# VSCard_v3.net
KiCad netlist of a schematic drawn in EAGLE
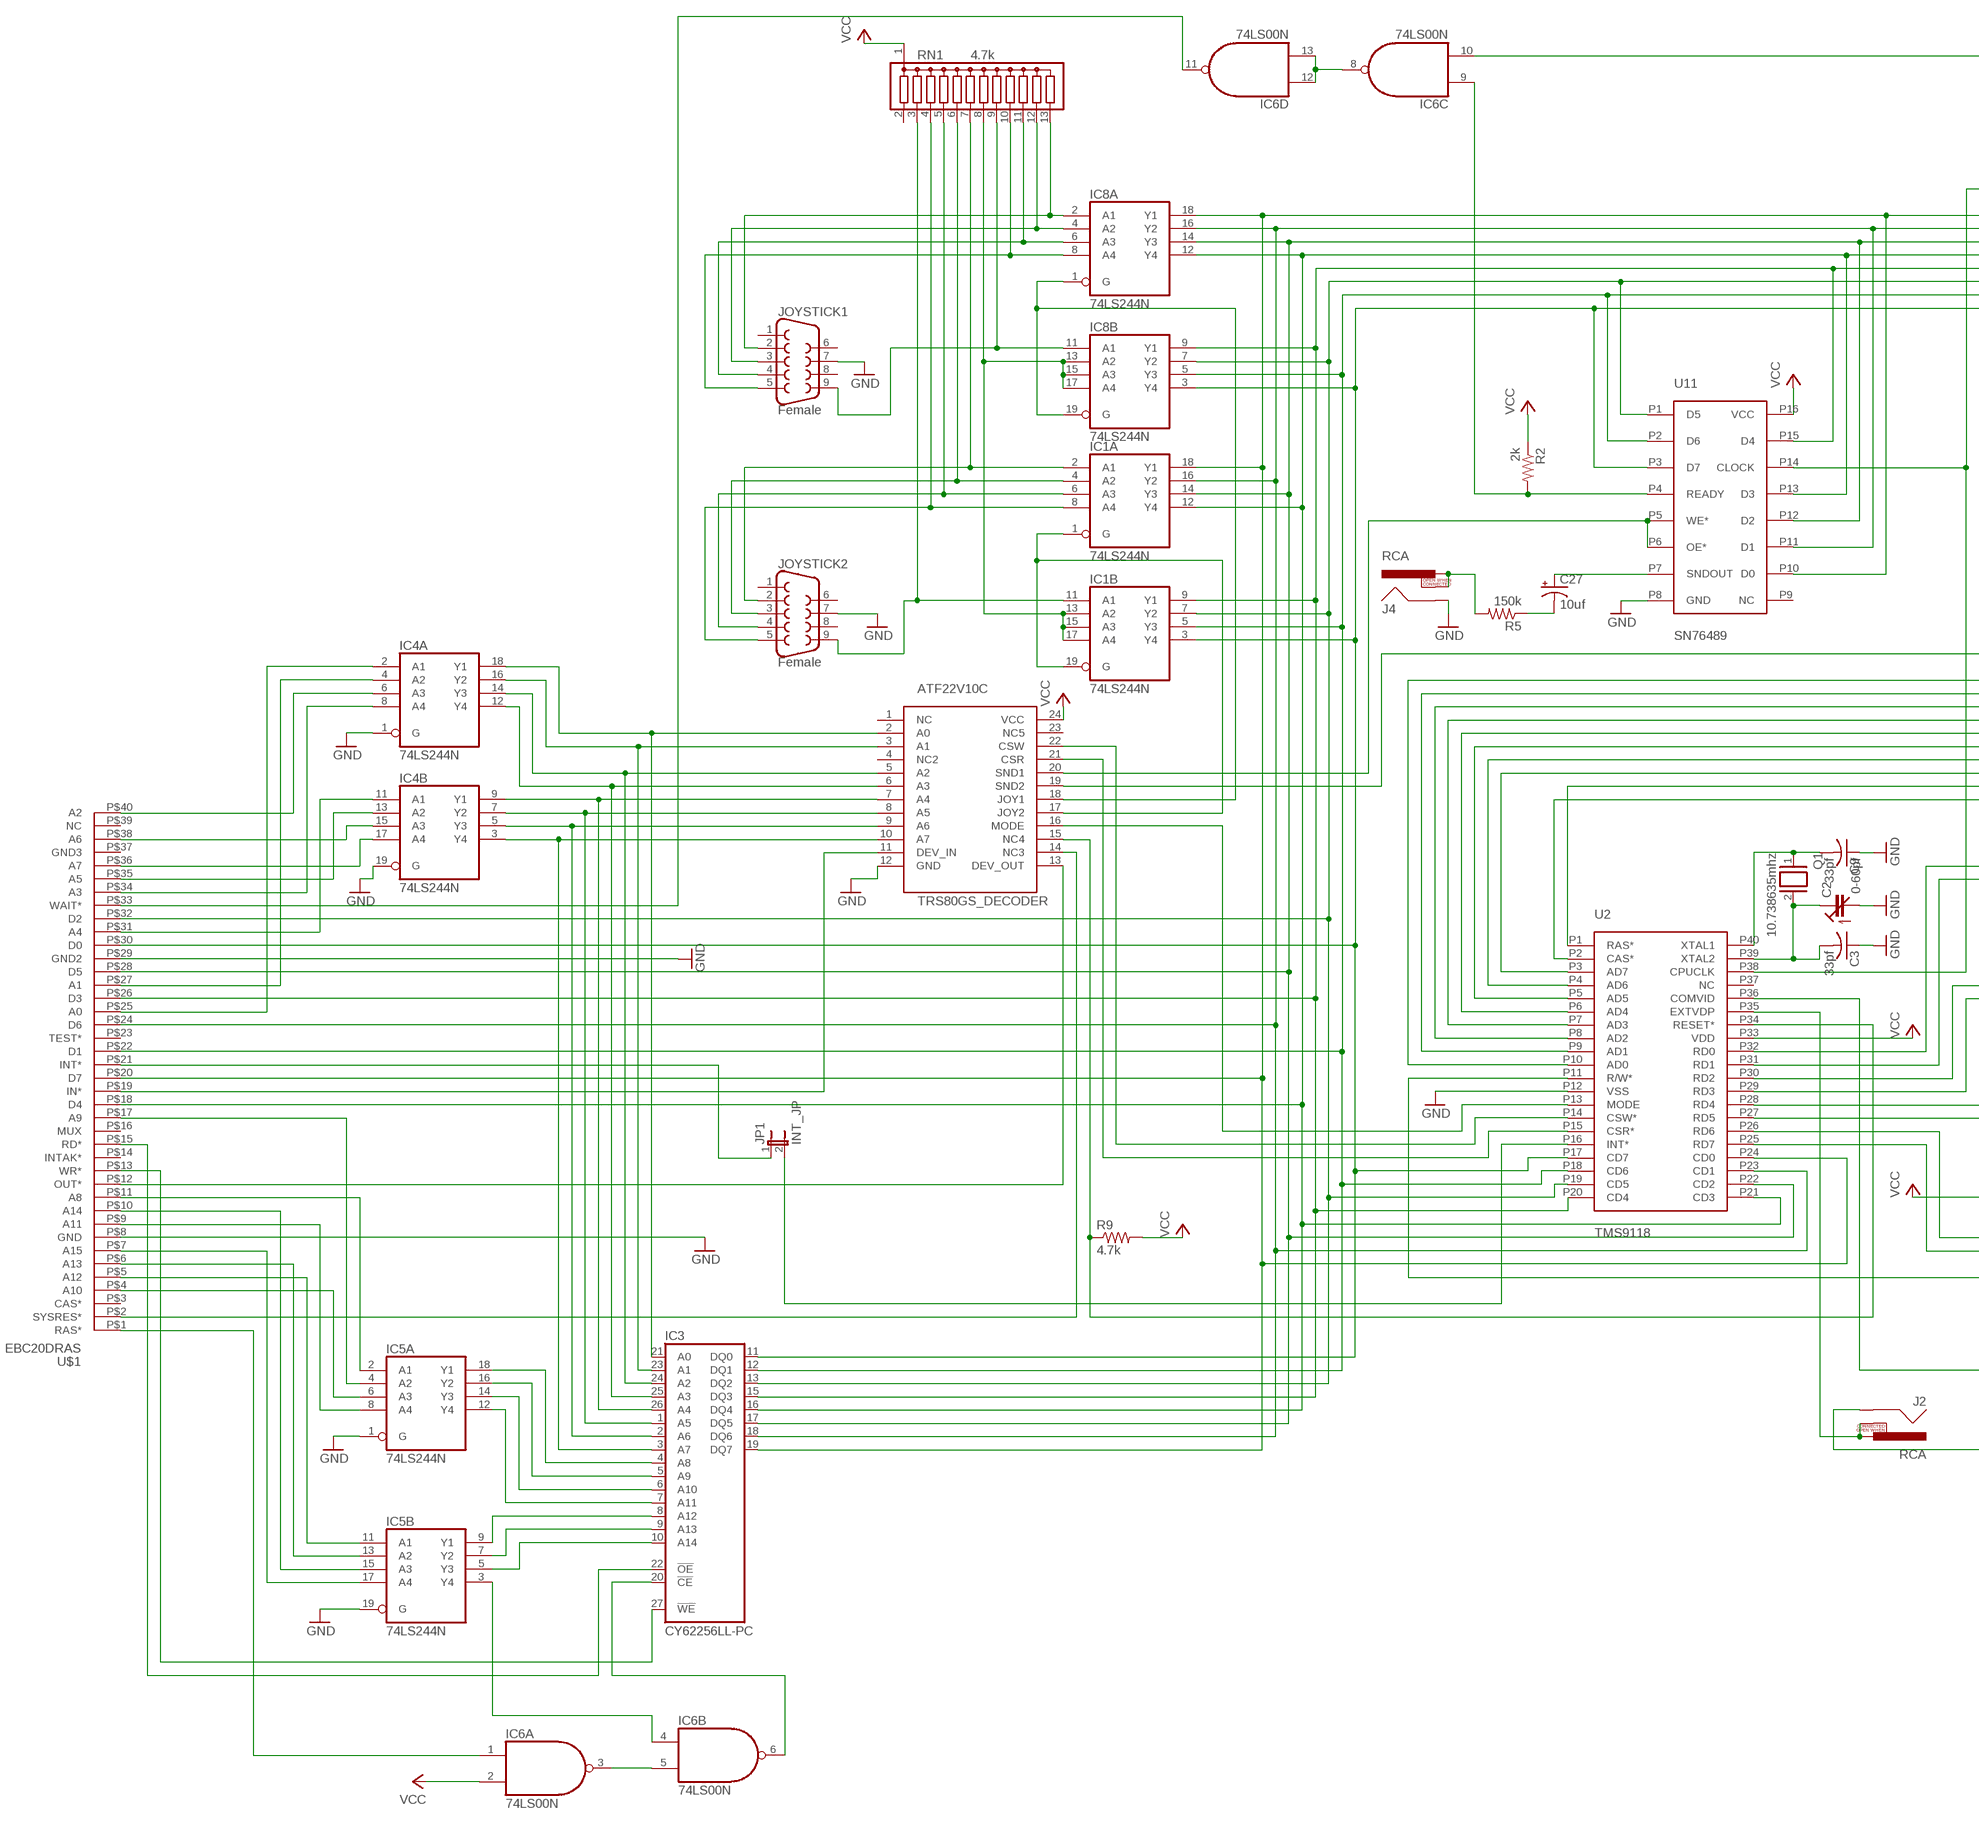
[diagram p0: schematic, sheet 1, part 1 of 2]
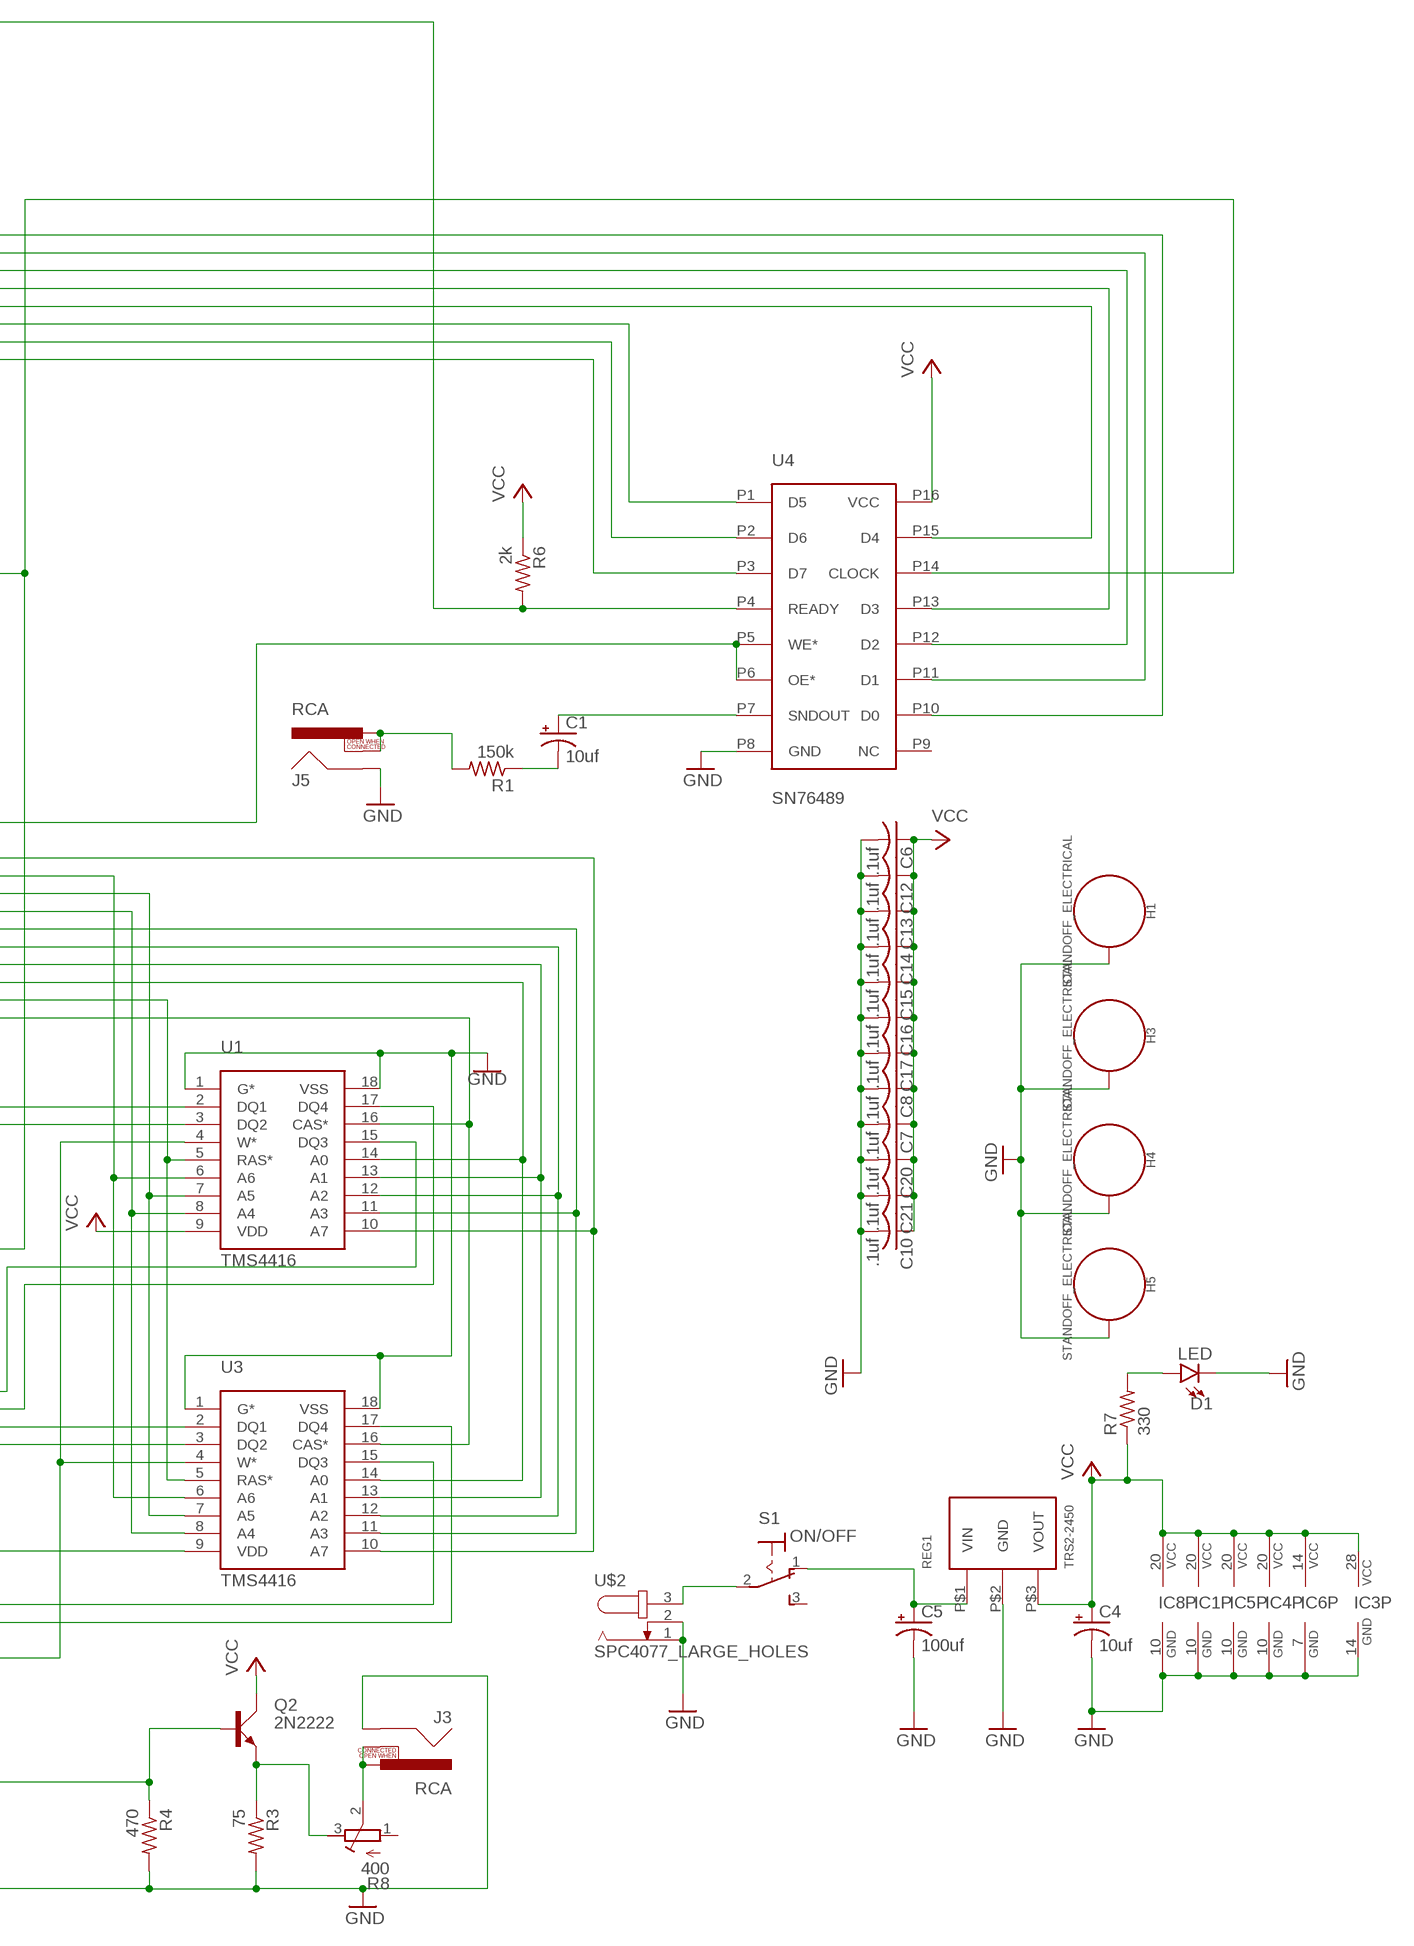
[diagram p1: schematic, sheet 1, part 2 of 2]

(export (version "E")
  (design (tool "Eeschema 10.0.6"))
  (components
    (comp (ref "ATF22V10C")
      (value "TRS80GS_DECODER")
      (footprint "eagle-import:DIP24SKI")
      (libsource (lib "eagle-import") (part "TRS80GS_DECODER"))
    )
    (comp (ref "C1")
      (value "10uf")
      (footprint "eagle-import:E2,5-6")
      (libsource (lib "eagle-import") (part "resistor_348_CPOL-USE2.5-6"))
    )
    (comp (ref "C2")
      (value "0-60pf")
      (footprint "eagle-import:CTRIM3050.504")
      (libsource (lib "eagle-import") (part "C-TRIMM3050.504"))
    )
    (comp (ref "C3")
      (value "33pf")
      (footprint "eagle-import:C050-050X075")
      (libsource (lib "eagle-import") (part "C-US050-050X075"))
    )
    (comp (ref "C4")
      (value "10uf")
      (footprint "eagle-import:E2,5-5")
      (libsource (lib "eagle-import") (part "resistor_348_CPOL-USE2.5-5"))
    )
    (comp (ref "C5")
      (value "100uf")
      (footprint "eagle-import:E3,5-10")
      (libsource (lib "eagle-import") (part "CPOL-USE3.5-10"))
    )
    (comp (ref "C6")
      (value ".1uf")
      (footprint "eagle-import:C025-025X050")
      (libsource (lib "eagle-import") (part "resistor_348_C-US025-025X050"))
    )
    (comp (ref "C7")
      (value ".1uf")
      (footprint "eagle-import:C025-025X050")
      (libsource (lib "eagle-import") (part "resistor_348_C-US025-025X050"))
    )
    (comp (ref "C8")
      (value ".1uf")
      (footprint "eagle-import:C025-025X050")
      (libsource (lib "eagle-import") (part "resistor_348_C-US025-025X050"))
    )
    (comp (ref "C9")
      (value "33pf")
      (footprint "eagle-import:C050-050X075")
      (libsource (lib "eagle-import") (part "C-US050-050X075"))
    )
    (comp (ref "C10")
      (value ".1uf")
      (footprint "eagle-import:C025-025X050")
      (libsource (lib "eagle-import") (part "resistor_348_C-US025-025X050"))
    )
    (comp (ref "C12")
      (value ".1uf")
      (footprint "eagle-import:C025-025X050")
      (libsource (lib "eagle-import") (part "resistor_348_C-US025-025X050"))
    )
    (comp (ref "C13")
      (value ".1uf")
      (footprint "eagle-import:C025-025X050")
      (libsource (lib "eagle-import") (part "resistor_348_C-US025-025X050"))
    )
    (comp (ref "C14")
      (value ".1uf")
      (footprint "eagle-import:C025-025X050")
      (libsource (lib "eagle-import") (part "resistor_348_C-US025-025X050"))
    )
    (comp (ref "C15")
      (value ".1uf")
      (footprint "eagle-import:C025-025X050")
      (libsource (lib "eagle-import") (part "resistor_348_C-US025-025X050"))
    )
    (comp (ref "C16")
      (value ".1uf")
      (footprint "eagle-import:C025-025X050")
      (libsource (lib "eagle-import") (part "resistor_348_C-US025-025X050"))
    )
    (comp (ref "C17")
      (value ".1uf")
      (footprint "eagle-import:C025-025X050")
      (libsource (lib "eagle-import") (part "resistor_348_C-US025-025X050"))
    )
    (comp (ref "C20")
      (value ".1uf")
      (footprint "eagle-import:C025-025X050")
      (libsource (lib "eagle-import") (part "resistor_348_C-US025-025X050"))
    )
    (comp (ref "C21")
      (value ".1uf")
      (footprint "eagle-import:C025-025X050")
      (libsource (lib "eagle-import") (part "resistor_348_C-US025-025X050"))
    )
    (comp (ref "C27")
      (value "10uf")
      (footprint "eagle-import:E2,5-6")
      (libsource (lib "eagle-import") (part "resistor_348_CPOL-USE2.5-6"))
    )
    (comp (ref "D1")
      (value "LED")
      (footprint "eagle-import:LED_3MM")
      (libsource (lib "eagle-import") (part "LED3MM"))
    )
    (comp (ref "H1")
      (value "STANDOFF_ELECTRICAL")
      (footprint "eagle-import:STANDOFF-ELECTRICAL")
      (libsource (lib "eagle-import") (part "STANDOFF_ELECTRICAL"))
    )
    (comp (ref "H3")
      (value "STANDOFF_ELECTRICAL")
      (footprint "eagle-import:STANDOFF-ELECTRICAL")
      (libsource (lib "eagle-import") (part "STANDOFF_ELECTRICAL"))
    )
    (comp (ref "H4")
      (value "STANDOFF_ELECTRICAL")
      (footprint "eagle-import:STANDOFF-ELECTRICAL")
      (libsource (lib "eagle-import") (part "STANDOFF_ELECTRICAL"))
    )
    (comp (ref "H5")
      (value "STANDOFF_ELECTRICAL")
      (footprint "eagle-import:STANDOFF-ELECTRICAL")
      (libsource (lib "eagle-import") (part "STANDOFF_ELECTRICAL"))
    )
    (comp (ref "IC1")
      (value "74LS244N")
      (footprint "eagle-import:DIL20")
      (libsource (lib "eagle-import") (part "74244NLS"))
    )
    (comp (ref "IC3")
      (value "CY62256LL-PC")
      (footprint "eagle-import:DIL28-6")
      (libsource (lib "eagle-import") (part "CY62256LL-?PC"))
    )
    (comp (ref "IC4")
      (value "74LS244N")
      (footprint "eagle-import:DIL20")
      (libsource (lib "eagle-import") (part "74244NLS"))
    )
    (comp (ref "IC5")
      (value "74LS244N")
      (footprint "eagle-import:DIL20")
      (libsource (lib "eagle-import") (part "74244NLS"))
    )
    (comp (ref "IC6")
      (value "74LS00N")
      (footprint "eagle-import:DIL14")
      (libsource (lib "eagle-import") (part "7400NLS"))
    )
    (comp (ref "IC8")
      (value "74LS244N")
      (footprint "eagle-import:DIL20")
      (libsource (lib "eagle-import") (part "74244NLS"))
    )
    (comp (ref "J2")
      (value "RCA")
      (footprint "eagle-import:RCA")
      (libsource (lib "eagle-import") (part "RCA"))
    )
    (comp (ref "J3")
      (value "RCA")
      (footprint "eagle-import:RCA")
      (libsource (lib "eagle-import") (part "RCA"))
    )
    (comp (ref "J4")
      (value "RCA")
      (footprint "eagle-import:RCA")
      (libsource (lib "eagle-import") (part "RCA"))
    )
    (comp (ref "J5")
      (value "RCA")
      (footprint "eagle-import:RCA")
      (libsource (lib "eagle-import") (part "RCA"))
    )
    (comp (ref "JOYSTICK1")
      (value "Female")
      (footprint "eagle-import:DB9")
      (libsource (lib "eagle-import") (part "DB9FEMALE"))
    )
    (comp (ref "JOYSTICK2")
      (value "Female")
      (footprint "eagle-import:DB9")
      (libsource (lib "eagle-import") (part "DB9FEMALE"))
    )
    (comp (ref "JP1")
      (value "INT_JP")
      (footprint "eagle-import:JP1")
      (libsource (lib "eagle-import") (part "JP1E"))
    )
    (comp (ref "Q1")
      (value "10.738635mhz")
      (footprint "eagle-import:QS")
      (libsource (lib "eagle-import") (part "XTAL/S"))
    )
    (comp (ref "Q2")
      (value "2N2222")
      (footprint "eagle-import:TO18A")
      (libsource (lib "eagle-import") (part "2N2222"))
    )
    (comp (ref "R1")
      (value "150k")
      (footprint "eagle-import:0207_2V")
      (libsource (lib "eagle-import") (part "R-US_0207/2V"))
    )
    (comp (ref "R2")
      (value "2k")
      (footprint "eagle-import:0207_2V")
      (libsource (lib "eagle-import") (part "R-US_0207/2V"))
    )
    (comp (ref "R3")
      (value "75")
      (footprint "eagle-import:0207_2V")
      (libsource (lib "eagle-import") (part "R-US_0207/2V"))
    )
    (comp (ref "R4")
      (value "470")
      (footprint "eagle-import:0207_2V")
      (libsource (lib "eagle-import") (part "R-US_0207/2V"))
    )
    (comp (ref "R5")
      (value "150k")
      (footprint "eagle-import:0207_2V")
      (libsource (lib "eagle-import") (part "R-US_0207/2V"))
    )
    (comp (ref "R6")
      (value "2k")
      (footprint "eagle-import:0207_2V")
      (libsource (lib "eagle-import") (part "R-US_0207/2V"))
    )
    (comp (ref "R7")
      (value "330")
      (footprint "eagle-import:0309V")
      (libsource (lib "eagle-import") (part "R-US_0309/V"))
    )
    (comp (ref "R8")
      (value "400")
      (footprint "eagle-import:RTRIM64W")
      (libsource (lib "eagle-import") (part "R-TRIMM64W"))
    )
    (comp (ref "R9")
      (value "4.7k")
      (footprint "eagle-import:0207_2V")
      (libsource (lib "eagle-import") (part "R-US_0207/2V"))
    )
    (comp (ref "REG1")
      (value "TRS2-2450")
      (footprint "eagle-import:TRACON_REG")
      (libsource (lib "eagle-import") (part "TRS2-2450"))
    )
    (comp (ref "RN1")
      (value "4.7k")
      (footprint "eagle-import:SIL13")
      (libsource (lib "eagle-import") (part "G12R"))
    )
    (comp (ref "S1")
      (value "ON/OFF")
      (footprint "eagle-import:320-916")
      (libsource (lib "eagle-import") (part "320-916"))
    )
    (comp (ref "U$1")
      (value "EBC20DRAS")
      (footprint "eagle-import:EBC20DRAS")
      (libsource (lib "eagle-import") (part "EBC20DRAS"))
    )
    (comp (ref "U$2")
      (value "SPC4077_LARGE_HOLES")
      (footprint "eagle-import:SPC4077")
      (libsource (lib "eagle-import") (part "SPC4077_LARGE_HOLES"))
    )
    (comp (ref "U1")
      (value "TMS4416")
      (footprint "eagle-import:DIP18")
      (libsource (lib "eagle-import") (part "TMS4416"))
    )
    (comp (ref "U2")
      (value "TMS9118")
      (footprint "eagle-import:DIP40_MCU")
      (libsource (lib "eagle-import") (part "TMS9118"))
    )
    (comp (ref "U3")
      (value "TMS4416")
      (footprint "eagle-import:DIP18")
      (libsource (lib "eagle-import") (part "TMS4416"))
    )
    (comp (ref "U4")
      (value "SN76489")
      (footprint "eagle-import:DIP16")
      (libsource (lib "eagle-import") (part "SN76489"))
    )
    (comp (ref "U11")
      (value "SN76489")
      (footprint "eagle-import:DIP16")
      (libsource (lib "eagle-import") (part "SN76489"))
    )
  )
  (nets
    (net (code "1") (name "GND") (class "Default")
      (node (ref "ATF22V10C") (pin "12") (pinfunction "GND_12") (pintype "bidirectional"))
      (node (ref "C10") (pin "2") (pinfunction "2_2") (pintype "passive"))
      (node (ref "C12") (pin "2") (pinfunction "2_2") (pintype "passive"))
      (node (ref "C13") (pin "2") (pinfunction "2_2") (pintype "passive"))
      (node (ref "C14") (pin "2") (pinfunction "2_2") (pintype "passive"))
      (node (ref "C15") (pin "2") (pinfunction "2_2") (pintype "passive"))
      (node (ref "C16") (pin "2") (pinfunction "2_2") (pintype "passive"))
      (node (ref "C17") (pin "2") (pinfunction "2_2") (pintype "passive"))
      (node (ref "C2") (pin "2") (pinfunction "A_2") (pintype "passive"))
      (node (ref "C20") (pin "2") (pinfunction "2_2") (pintype "passive"))
      (node (ref "C21") (pin "2") (pinfunction "2_2") (pintype "passive"))
      (node (ref "C3") (pin "1") (pinfunction "1_1") (pintype "passive"))
      (node (ref "C4") (pin "-") (pinfunction "-_-") (pintype "passive"))
      (node (ref "C5") (pin "-") (pinfunction "-_-") (pintype "passive"))
      (node (ref "C6") (pin "2") (pinfunction "2_2") (pintype "passive"))
      (node (ref "C7") (pin "2") (pinfunction "2_2") (pintype "passive"))
      (node (ref "C8") (pin "2") (pinfunction "2_2") (pintype "passive"))
      (node (ref "C9") (pin "1") (pinfunction "1_1") (pintype "passive"))
      (node (ref "D1") (pin "K") (pinfunction "C_K") (pintype "passive"))
      (node (ref "H1") (pin "P1") (pinfunction "P$1_P1") (pintype "bidirectional"))
      (node (ref "H3") (pin "P1") (pinfunction "P$1_P1") (pintype "bidirectional"))
      (node (ref "H4") (pin "P1") (pinfunction "P$1_P1") (pintype "bidirectional"))
      (node (ref "H5") (pin "P1") (pinfunction "P$1_P1") (pintype "bidirectional"))
      (node (ref "IC1") (pin "10") (pinfunction "GND_10") (pintype "power_in"))
      (node (ref "IC3") (pin "14") (pinfunction "GND_14") (pintype "power_in"))
      (node (ref "IC4") (pin "1") (pinfunction "G_1") (pintype "input"))
      (node (ref "IC4") (pin "10") (pinfunction "GND_10") (pintype "power_in"))
      (node (ref "IC4") (pin "19") (pinfunction "G_19") (pintype "input"))
      (node (ref "IC5") (pin "1") (pinfunction "G_1") (pintype "input"))
      (node (ref "IC5") (pin "10") (pinfunction "GND_10") (pintype "power_in"))
      (node (ref "IC5") (pin "19") (pinfunction "G_19") (pintype "input"))
      (node (ref "IC6") (pin "7") (pinfunction "GND_7") (pintype "power_in"))
      (node (ref "IC8") (pin "10") (pinfunction "GND_10") (pintype "power_in"))
      (node (ref "J2") (pin "SHELL") (pinfunction "SHELL_SHELL") (pintype "bidirectional"))
      (node (ref "J3") (pin "SHELL") (pinfunction "SHELL_SHELL") (pintype "bidirectional"))
      (node (ref "J4") (pin "SHELL") (pinfunction "SHELL_SHELL") (pintype "bidirectional"))
      (node (ref "J5") (pin "SHELL") (pinfunction "SHELL_SHELL") (pintype "bidirectional"))
      (node (ref "JOYSTICK1") (pin "7") (pinfunction "7_7") (pintype "passive"))
      (node (ref "JOYSTICK2") (pin "7") (pinfunction "7_7") (pintype "passive"))
      (node (ref "R3") (pin "2") (pinfunction "2_2") (pintype "passive"))
      (node (ref "R4") (pin "2") (pinfunction "2_2") (pintype "passive"))
      (node (ref "REG1") (pin "P$2") (pinfunction "GND_P$2") (pintype "bidirectional"))
      (node (ref "U$1") (pin "P$29") (pinfunction "GND2_P$29") (pintype "bidirectional"))
      (node (ref "U$1") (pin "P$8") (pinfunction "GND_P$8") (pintype "bidirectional"))
      (node (ref "U$2") (pin "1") (pinfunction "1_1") (pintype "passive"))
      (node (ref "U$2") (pin "2") (pinfunction "2_2") (pintype "passive"))
      (node (ref "U1") (pin "1") (pinfunction "G*_1") (pintype "bidirectional"))
      (node (ref "U1") (pin "18") (pinfunction "VSS_18") (pintype "bidirectional"))
      (node (ref "U11") (pin "P8") (pinfunction "GND_P8") (pintype "bidirectional"))
      (node (ref "U2") (pin "P12") (pinfunction "VSS_P12") (pintype "bidirectional"))
      (node (ref "U3") (pin "1") (pinfunction "G*_1") (pintype "bidirectional"))
      (node (ref "U3") (pin "18") (pinfunction "VSS_18") (pintype "bidirectional"))
      (node (ref "U4") (pin "P8") (pinfunction "GND_P8") (pintype "bidirectional"))
    )
    (net (code "2") (name "Net-(ATF22V10C-A0)") (class "Default")
      (node (ref "ATF22V10C") (pin "2") (pinfunction "A0_2") (pintype "bidirectional"))
      (node (ref "IC3") (pin "21") (pinfunction "A0_21") (pintype "input"))
      (node (ref "IC4") (pin "18") (pinfunction "Y1_18") (pintype "tri_state"))
    )
    (net (code "3") (name "Net-(ATF22V10C-A1)") (class "Default")
      (node (ref "ATF22V10C") (pin "3") (pinfunction "A1_3") (pintype "bidirectional"))
      (node (ref "IC3") (pin "23") (pinfunction "A1_23") (pintype "input"))
      (node (ref "IC4") (pin "16") (pinfunction "Y2_16") (pintype "tri_state"))
    )
    (net (code "4") (name "Net-(ATF22V10C-A2)") (class "Default")
      (node (ref "ATF22V10C") (pin "5") (pinfunction "A2_5") (pintype "bidirectional"))
      (node (ref "IC3") (pin "24") (pinfunction "A2_24") (pintype "input"))
      (node (ref "IC4") (pin "14") (pinfunction "Y3_14") (pintype "tri_state"))
    )
    (net (code "5") (name "Net-(ATF22V10C-A3)") (class "Default")
      (node (ref "ATF22V10C") (pin "6") (pinfunction "A3_6") (pintype "bidirectional"))
      (node (ref "IC3") (pin "25") (pinfunction "A3_25") (pintype "input"))
      (node (ref "IC4") (pin "12") (pinfunction "Y4_12") (pintype "tri_state"))
    )
    (net (code "6") (name "Net-(ATF22V10C-A4)") (class "Default")
      (node (ref "ATF22V10C") (pin "7") (pinfunction "A4_7") (pintype "bidirectional"))
      (node (ref "IC3") (pin "26") (pinfunction "A4_26") (pintype "input"))
      (node (ref "IC4") (pin "9") (pinfunction "Y1_9") (pintype "tri_state"))
    )
    (net (code "7") (name "Net-(ATF22V10C-A5)") (class "Default")
      (node (ref "ATF22V10C") (pin "8") (pinfunction "A5_8") (pintype "bidirectional"))
      (node (ref "IC3") (pin "1") (pinfunction "A5_1") (pintype "input"))
      (node (ref "IC4") (pin "7") (pinfunction "Y2_7") (pintype "tri_state"))
    )
    (net (code "8") (name "Net-(ATF22V10C-A6)") (class "Default")
      (node (ref "ATF22V10C") (pin "9") (pinfunction "A6_9") (pintype "bidirectional"))
      (node (ref "IC3") (pin "2") (pinfunction "A6_2") (pintype "input"))
      (node (ref "IC4") (pin "5") (pinfunction "Y3_5") (pintype "tri_state"))
    )
    (net (code "9") (name "Net-(ATF22V10C-A7)") (class "Default")
      (node (ref "ATF22V10C") (pin "10") (pinfunction "A7_10") (pintype "bidirectional"))
      (node (ref "IC3") (pin "3") (pinfunction "A7_3") (pintype "input"))
      (node (ref "IC4") (pin "3") (pinfunction "Y4_3") (pintype "tri_state"))
    )
    (net (code "10") (name "Net-(ATF22V10C-CSR)") (class "Default")
      (node (ref "ATF22V10C") (pin "21") (pinfunction "CSR_21") (pintype "bidirectional"))
      (node (ref "U2") (pin "P15") (pinfunction "CSR*_P15") (pintype "bidirectional"))
    )
    (net (code "11") (name "Net-(ATF22V10C-CSW)") (class "Default")
      (node (ref "ATF22V10C") (pin "22") (pinfunction "CSW_22") (pintype "bidirectional"))
      (node (ref "U2") (pin "P14") (pinfunction "CSW*_P14") (pintype "bidirectional"))
    )
    (net (code "12") (name "Net-(ATF22V10C-DEV_IN)") (class "Default")
      (node (ref "ATF22V10C") (pin "11") (pinfunction "DEV_IN_11") (pintype "bidirectional"))
      (node (ref "U$1") (pin "P$19") (pinfunction "IN*_P$19") (pintype "bidirectional"))
    )
    (net (code "13") (name "Net-(ATF22V10C-DEV_OUT)") (class "Default")
      (node (ref "ATF22V10C") (pin "13") (pinfunction "DEV_OUT_13") (pintype "bidirectional"))
      (node (ref "U$1") (pin "P$12") (pinfunction "OUT*_P$12") (pintype "bidirectional"))
    )
    (net (code "14") (name "Net-(ATF22V10C-JOY1)") (class "Default")
      (node (ref "ATF22V10C") (pin "18") (pinfunction "JOY1_18") (pintype "bidirectional"))
      (node (ref "IC8") (pin "1") (pinfunction "G_1") (pintype "input"))
      (node (ref "IC8") (pin "19") (pinfunction "G_19") (pintype "input"))
    )
    (net (code "15") (name "Net-(ATF22V10C-JOY2)") (class "Default")
      (node (ref "ATF22V10C") (pin "17") (pinfunction "JOY2_17") (pintype "bidirectional"))
      (node (ref "IC1") (pin "1") (pinfunction "G_1") (pintype "input"))
      (node (ref "IC1") (pin "19") (pinfunction "G_19") (pintype "input"))
    )
    (net (code "16") (name "Net-(ATF22V10C-MODE)") (class "Default")
      (node (ref "ATF22V10C") (pin "16") (pinfunction "MODE_16") (pintype "bidirectional"))
      (node (ref "U2") (pin "P13") (pinfunction "MODE_P13") (pintype "bidirectional"))
    )
    (net (code "17") (name "Net-(ATF22V10C-NC3)") (class "Default")
      (node (ref "ATF22V10C") (pin "14") (pinfunction "NC3_14") (pintype "bidirectional"))
      (node (ref "U$1") (pin "P$2") (pinfunction "SYSRES*_P$2") (pintype "bidirectional"))
    )
    (net (code "18") (name "Net-(ATF22V10C-NC4)") (class "Default")
      (node (ref "ATF22V10C") (pin "15") (pinfunction "NC4_15") (pintype "bidirectional"))
      (node (ref "R9") (pin "1") (pinfunction "1_1") (pintype "passive"))
      (node (ref "U2") (pin "P34") (pinfunction "RESET*_P34") (pintype "bidirectional"))
    )
    (net (code "19") (name "Net-(ATF22V10C-SND1)") (class "Default")
      (node (ref "ATF22V10C") (pin "20") (pinfunction "SND1_20") (pintype "bidirectional"))
      (node (ref "U11") (pin "P5") (pinfunction "WE*_P5") (pintype "bidirectional"))
      (node (ref "U11") (pin "P6") (pinfunction "OE*_P6") (pintype "bidirectional"))
    )
    (net (code "20") (name "Net-(ATF22V10C-SND2)") (class "Default")
      (node (ref "ATF22V10C") (pin "19") (pinfunction "SND2_19") (pintype "bidirectional"))
      (node (ref "U4") (pin "P5") (pinfunction "WE*_P5") (pintype "bidirectional"))
      (node (ref "U4") (pin "P6") (pinfunction "OE*_P6") (pintype "bidirectional"))
    )
    (net (code "21") (name "Net-(C1-Pad-)") (class "Default")
      (node (ref "C1") (pin "-") (pinfunction "-_-") (pintype "passive"))
      (node (ref "R1") (pin "1") (pinfunction "1_1") (pintype "passive"))
    )
    (net (code "22") (name "Net-(C2-E)") (class "Default")
      (node (ref "C2") (pin "1") (pinfunction "E_1") (pintype "passive"))
      (node (ref "C3") (pin "2") (pinfunction "2_2") (pintype "passive"))
      (node (ref "Q1") (pin "2") (pinfunction "2_2") (pintype "passive"))
      (node (ref "U2") (pin "P39") (pinfunction "XTAL2_P39") (pintype "bidirectional"))
    )
    (net (code "23") (name "Net-(C27-Pad-)") (class "Default")
      (node (ref "C27") (pin "-") (pinfunction "-_-") (pintype "passive"))
      (node (ref "R5") (pin "1") (pinfunction "1_1") (pintype "passive"))
    )
    (net (code "24") (name "Net-(D1-PadA)") (class "Default")
      (node (ref "D1") (pin "A") (pinfunction "A_A") (pintype "passive"))
      (node (ref "R7") (pin "2") (pinfunction "2_2") (pintype "passive"))
    )
    (net (code "25") (name "Net-(IC1A-A1)") (class "Default")
      (node (ref "IC1") (pin "2") (pinfunction "A1_2") (pintype "input"))
      (node (ref "JOYSTICK2") (pin "2") (pinfunction "2_2") (pintype "passive"))
      (node (ref "RN1") (pin "7") (pinfunction "7_7") (pintype "passive"))
    )
    (net (code "26") (name "Net-(IC1A-A2)") (class "Default")
      (node (ref "IC1") (pin "4") (pinfunction "A2_4") (pintype "input"))
      (node (ref "JOYSTICK2") (pin "3") (pinfunction "3_3") (pintype "passive"))
      (node (ref "RN1") (pin "6") (pinfunction "6_6") (pintype "passive"))
    )
    (net (code "27") (name "Net-(IC1A-A3)") (class "Default")
      (node (ref "IC1") (pin "6") (pinfunction "A3_6") (pintype "input"))
      (node (ref "JOYSTICK2") (pin "4") (pinfunction "4_4") (pintype "passive"))
      (node (ref "RN1") (pin "5") (pinfunction "5_5") (pintype "passive"))
    )
    (net (code "28") (name "Net-(IC1A-A4)") (class "Default")
      (node (ref "IC1") (pin "8") (pinfunction "A4_8") (pintype "input"))
      (node (ref "JOYSTICK2") (pin "5") (pinfunction "5_5") (pintype "passive"))
      (node (ref "RN1") (pin "4") (pinfunction "4_4") (pintype "passive"))
    )
    (net (code "29") (name "Net-(IC1A-Y1)") (class "Default")
      (node (ref "IC1") (pin "18") (pinfunction "Y1_18") (pintype "tri_state"))
      (node (ref "IC3") (pin "19") (pinfunction "DQ7_19") (pintype "bidirectional"))
      (node (ref "IC8") (pin "18") (pinfunction "Y1_18") (pintype "tri_state"))
      (node (ref "U$1") (pin "P$20") (pinfunction "D7_P$20") (pintype "bidirectional"))
      (node (ref "U11") (pin "P10") (pinfunction "D0_P10") (pintype "bidirectional"))
      (node (ref "U2") (pin "P24") (pinfunction "CD0_P24") (pintype "bidirectional"))
      (node (ref "U4") (pin "P10") (pinfunction "D0_P10") (pintype "bidirectional"))
    )
    (net (code "30") (name "Net-(IC1A-Y2)") (class "Default")
      (node (ref "IC1") (pin "16") (pinfunction "Y2_16") (pintype "tri_state"))
      (node (ref "IC3") (pin "18") (pinfunction "DQ6_18") (pintype "bidirectional"))
      (node (ref "IC8") (pin "16") (pinfunction "Y2_16") (pintype "tri_state"))
      (node (ref "U$1") (pin "P$24") (pinfunction "D6_P$24") (pintype "bidirectional"))
      (node (ref "U11") (pin "P11") (pinfunction "D1_P11") (pintype "bidirectional"))
      (node (ref "U2") (pin "P23") (pinfunction "CD1_P23") (pintype "bidirectional"))
      (node (ref "U4") (pin "P11") (pinfunction "D1_P11") (pintype "bidirectional"))
    )
    (net (code "31") (name "Net-(IC1A-Y3)") (class "Default")
      (node (ref "IC1") (pin "14") (pinfunction "Y3_14") (pintype "tri_state"))
      (node (ref "IC3") (pin "17") (pinfunction "DQ5_17") (pintype "bidirectional"))
      (node (ref "IC8") (pin "14") (pinfunction "Y3_14") (pintype "tri_state"))
      (node (ref "U$1") (pin "P$28") (pinfunction "D5_P$28") (pintype "bidirectional"))
      (node (ref "U11") (pin "P12") (pinfunction "D2_P12") (pintype "bidirectional"))
      (node (ref "U2") (pin "P22") (pinfunction "CD2_P22") (pintype "bidirectional"))
      (node (ref "U4") (pin "P12") (pinfunction "D2_P12") (pintype "bidirectional"))
    )
    (net (code "32") (name "Net-(IC1A-Y4)") (class "Default")
      (node (ref "IC1") (pin "12") (pinfunction "Y4_12") (pintype "tri_state"))
      (node (ref "IC3") (pin "16") (pinfunction "DQ4_16") (pintype "bidirectional"))
      (node (ref "IC8") (pin "12") (pinfunction "Y4_12") (pintype "tri_state"))
      (node (ref "U$1") (pin "P$18") (pinfunction "D4_P$18") (pintype "bidirectional"))
      (node (ref "U11") (pin "P13") (pinfunction "D3_P13") (pintype "bidirectional"))
      (node (ref "U2") (pin "P21") (pinfunction "CD3_P21") (pintype "bidirectional"))
      (node (ref "U4") (pin "P13") (pinfunction "D3_P13") (pintype "bidirectional"))
    )
    (net (code "33") (name "Net-(IC1B-A1)") (class "Default")
      (node (ref "IC1") (pin "11") (pinfunction "A1_11") (pintype "input"))
      (node (ref "JOYSTICK2") (pin "9") (pinfunction "9_9") (pintype "passive"))
      (node (ref "RN1") (pin "3") (pinfunction "3_3") (pintype "passive"))
    )
    (net (code "34") (name "Net-(IC1B-A2)") (class "Default")
      (node (ref "IC1") (pin "13") (pinfunction "A2_13") (pintype "input"))
      (node (ref "IC1") (pin "15") (pinfunction "A3_15") (pintype "input"))
      (node (ref "IC1") (pin "17") (pinfunction "A4_17") (pintype "input"))
      (node (ref "IC8") (pin "13") (pinfunction "A2_13") (pintype "input"))
      (node (ref "IC8") (pin "15") (pinfunction "A3_15") (pintype "input"))
      (node (ref "IC8") (pin "17") (pinfunction "A4_17") (pintype "input"))
      (node (ref "RN1") (pin "8") (pinfunction "8_8") (pintype "passive"))
    )
    (net (code "35") (name "Net-(IC1B-Y1)") (class "Default")
      (node (ref "IC1") (pin "9") (pinfunction "Y1_9") (pintype "tri_state"))
      (node (ref "IC3") (pin "15") (pinfunction "DQ3_15") (pintype "bidirectional"))
      (node (ref "IC8") (pin "9") (pinfunction "Y1_9") (pintype "tri_state"))
      (node (ref "U$1") (pin "P$26") (pinfunction "D3_P$26") (pintype "bidirectional"))
      (node (ref "U11") (pin "P15") (pinfunction "D4_P15") (pintype "bidirectional"))
      (node (ref "U2") (pin "P20") (pinfunction "CD4_P20") (pintype "bidirectional"))
      (node (ref "U4") (pin "P15") (pinfunction "D4_P15") (pintype "bidirectional"))
    )
    (net (code "36") (name "Net-(IC1B-Y2)") (class "Default")
      (node (ref "IC1") (pin "7") (pinfunction "Y2_7") (pintype "tri_state"))
      (node (ref "IC3") (pin "13") (pinfunction "DQ2_13") (pintype "bidirectional"))
      (node (ref "IC8") (pin "7") (pinfunction "Y2_7") (pintype "tri_state"))
      (node (ref "U$1") (pin "P$32") (pinfunction "D2_P$32") (pintype "bidirectional"))
      (node (ref "U11") (pin "P1") (pinfunction "D5_P1") (pintype "bidirectional"))
      (node (ref "U2") (pin "P19") (pinfunction "CD5_P19") (pintype "bidirectional"))
      (node (ref "U4") (pin "P1") (pinfunction "D5_P1") (pintype "bidirectional"))
    )
    (net (code "37") (name "Net-(IC1B-Y3)") (class "Default")
      (node (ref "IC1") (pin "5") (pinfunction "Y3_5") (pintype "tri_state"))
      (node (ref "IC3") (pin "12") (pinfunction "DQ1_12") (pintype "bidirectional"))
      (node (ref "IC8") (pin "5") (pinfunction "Y3_5") (pintype "tri_state"))
      (node (ref "U$1") (pin "P$22") (pinfunction "D1_P$22") (pintype "bidirectional"))
      (node (ref "U11") (pin "P2") (pinfunction "D6_P2") (pintype "bidirectional"))
      (node (ref "U2") (pin "P18") (pinfunction "CD6_P18") (pintype "bidirectional"))
      (node (ref "U4") (pin "P2") (pinfunction "D6_P2") (pintype "bidirectional"))
    )
    (net (code "38") (name "Net-(IC1B-Y4)") (class "Default")
      (node (ref "IC1") (pin "3") (pinfunction "Y4_3") (pintype "tri_state"))
      (node (ref "IC3") (pin "11") (pinfunction "DQ0_11") (pintype "bidirectional"))
      (node (ref "IC8") (pin "3") (pinfunction "Y4_3") (pintype "tri_state"))
      (node (ref "U$1") (pin "P$30") (pinfunction "D0_P$30") (pintype "bidirectional"))
      (node (ref "U11") (pin "P3") (pinfunction "D7_P3") (pintype "bidirectional"))
      (node (ref "U2") (pin "P17") (pinfunction "CD7_P17") (pintype "bidirectional"))
      (node (ref "U4") (pin "P3") (pinfunction "D7_P3") (pintype "bidirectional"))
    )
    (net (code "39") (name "Net-(IC3A-A8)") (class "Default")
      (node (ref "IC3") (pin "4") (pinfunction "A8_4") (pintype "input"))
      (node (ref "IC5") (pin "18") (pinfunction "Y1_18") (pintype "tri_state"))
    )
    (net (code "40") (name "Net-(IC3A-A9)") (class "Default")
      (node (ref "IC3") (pin "5") (pinfunction "A9_5") (pintype "input"))
      (node (ref "IC5") (pin "16") (pinfunction "Y2_16") (pintype "tri_state"))
    )
    (net (code "41") (name "Net-(IC3A-A10)") (class "Default")
      (node (ref "IC3") (pin "6") (pinfunction "A10_6") (pintype "input"))
      (node (ref "IC5") (pin "14") (pinfunction "Y3_14") (pintype "tri_state"))
    )
    (net (code "42") (name "Net-(IC3A-A11)") (class "Default")
      (node (ref "IC3") (pin "7") (pinfunction "A11_7") (pintype "input"))
      (node (ref "IC5") (pin "12") (pinfunction "Y4_12") (pintype "tri_state"))
    )
    (net (code "43") (name "Net-(IC3A-A12)") (class "Default")
      (node (ref "IC3") (pin "8") (pinfunction "A12_8") (pintype "input"))
      (node (ref "IC5") (pin "9") (pinfunction "Y1_9") (pintype "tri_state"))
    )
    (net (code "44") (name "Net-(IC3A-A13)") (class "Default")
      (node (ref "IC3") (pin "9") (pinfunction "A13_9") (pintype "input"))
      (node (ref "IC5") (pin "7") (pinfunction "Y2_7") (pintype "tri_state"))
    )
    (net (code "45") (name "Net-(IC3A-A14)") (class "Default")
      (node (ref "IC3") (pin "10") (pinfunction "A14_10") (pintype "input"))
      (node (ref "IC5") (pin "5") (pinfunction "Y3_5") (pintype "tri_state"))
    )
    (net (code "46") (name "Net-(IC3A-~{CE})") (class "Default")
      (node (ref "IC3") (pin "20") (pinfunction "~{CE}_20") (pintype "input"))
      (node (ref "IC6") (pin "6") (pinfunction "O_6") (pintype "output"))
    )
    (net (code "47") (name "Net-(IC3A-~{OE})") (class "Default")
      (node (ref "IC3") (pin "22") (pinfunction "~{OE}_22") (pintype "input"))
      (node (ref "U$1") (pin "P$15") (pinfunction "RD*_P$15") (pintype "bidirectional"))
    )
    (net (code "48") (name "Net-(IC3A-~{WE})") (class "Default")
      (node (ref "IC3") (pin "27") (pinfunction "~{WE}_27") (pintype "input"))
      (node (ref "U$1") (pin "P$13") (pinfunction "WR*_P$13") (pintype "bidirectional"))
    )
    (net (code "49") (name "Net-(IC4A-A1)") (class "Default")
      (node (ref "IC4") (pin "2") (pinfunction "A1_2") (pintype "input"))
      (node (ref "U$1") (pin "P$25") (pinfunction "A0_P$25") (pintype "bidirectional"))
    )
    (net (code "50") (name "Net-(IC4A-A2)") (class "Default")
      (node (ref "IC4") (pin "4") (pinfunction "A2_4") (pintype "input"))
      (node (ref "U$1") (pin "P$27") (pinfunction "A1_P$27") (pintype "bidirectional"))
    )
    (net (code "51") (name "Net-(IC4A-A3)") (class "Default")
      (node (ref "IC4") (pin "6") (pinfunction "A3_6") (pintype "input"))
      (node (ref "U$1") (pin "P$40") (pinfunction "A2_P$40") (pintype "bidirectional"))
    )
    (net (code "52") (name "Net-(IC4A-A4)") (class "Default")
      (node (ref "IC4") (pin "8") (pinfunction "A4_8") (pintype "input"))
      (node (ref "U$1") (pin "P$34") (pinfunction "A3_P$34") (pintype "bidirectional"))
    )
    (net (code "53") (name "Net-(IC4B-A1)") (class "Default")
      (node (ref "IC4") (pin "11") (pinfunction "A1_11") (pintype "input"))
      (node (ref "U$1") (pin "P$31") (pinfunction "A4_P$31") (pintype "bidirectional"))
    )
    (net (code "54") (name "Net-(IC4B-A2)") (class "Default")
      (node (ref "IC4") (pin "13") (pinfunction "A2_13") (pintype "input"))
      (node (ref "U$1") (pin "P$35") (pinfunction "A5_P$35") (pintype "bidirectional"))
    )
    (net (code "55") (name "Net-(IC4B-A3)") (class "Default")
      (node (ref "IC4") (pin "15") (pinfunction "A3_15") (pintype "input"))
      (node (ref "U$1") (pin "P$38") (pinfunction "A6_P$38") (pintype "bidirectional"))
    )
    (net (code "56") (name "Net-(IC4B-A4)") (class "Default")
      (node (ref "IC4") (pin "17") (pinfunction "A4_17") (pintype "input"))
      (node (ref "U$1") (pin "P$36") (pinfunction "A7_P$36") (pintype "bidirectional"))
    )
    (net (code "57") (name "Net-(IC5A-A1)") (class "Default")
      (node (ref "IC5") (pin "2") (pinfunction "A1_2") (pintype "input"))
      (node (ref "U$1") (pin "P$11") (pinfunction "A8_P$11") (pintype "bidirectional"))
    )
    (net (code "58") (name "Net-(IC5A-A2)") (class "Default")
      (node (ref "IC5") (pin "4") (pinfunction "A2_4") (pintype "input"))
      (node (ref "U$1") (pin "P$17") (pinfunction "A9_P$17") (pintype "bidirectional"))
    )
    (net (code "59") (name "Net-(IC5A-A3)") (class "Default")
      (node (ref "IC5") (pin "6") (pinfunction "A3_6") (pintype "input"))
      (node (ref "U$1") (pin "P$4") (pinfunction "A10_P$4") (pintype "bidirectional"))
    )
    (net (code "60") (name "Net-(IC5A-A4)") (class "Default")
      (node (ref "IC5") (pin "8") (pinfunction "A4_8") (pintype "input"))
      (node (ref "U$1") (pin "P$9") (pinfunction "A11_P$9") (pintype "bidirectional"))
    )
    (net (code "61") (name "Net-(IC5B-A1)") (class "Default")
      (node (ref "IC5") (pin "11") (pinfunction "A1_11") (pintype "input"))
      (node (ref "U$1") (pin "P$5") (pinfunction "A12_P$5") (pintype "bidirectional"))
    )
    (net (code "62") (name "Net-(IC5B-A2)") (class "Default")
      (node (ref "IC5") (pin "13") (pinfunction "A2_13") (pintype "input"))
      (node (ref "U$1") (pin "P$6") (pinfunction "A13_P$6") (pintype "bidirectional"))
    )
    (net (code "63") (name "Net-(IC5B-A3)") (class "Default")
      (node (ref "IC5") (pin "15") (pinfunction "A3_15") (pintype "input"))
      (node (ref "U$1") (pin "P$10") (pinfunction "A14_P$10") (pintype "bidirectional"))
    )
    (net (code "64") (name "Net-(IC5B-A4)") (class "Default")
      (node (ref "IC5") (pin "17") (pinfunction "A4_17") (pintype "input"))
      (node (ref "U$1") (pin "P$7") (pinfunction "A15_P$7") (pintype "bidirectional"))
    )
    (net (code "65") (name "Net-(IC5B-Y4)") (class "Default")
      (node (ref "IC5") (pin "3") (pinfunction "Y4_3") (pintype "tri_state"))
      (node (ref "IC6") (pin "4") (pinfunction "I0_4") (pintype "input"))
    )
    (net (code "66") (name "Net-(IC6A-I0)") (class "Default")
      (node (ref "IC6") (pin "1") (pinfunction "I0_1") (pintype "input"))
      (node (ref "U$1") (pin "P$1") (pinfunction "RAS*_P$1") (pintype "bidirectional"))
    )
    (net (code "67") (name "Net-(IC6A-O)") (class "Default")
      (node (ref "IC6") (pin "3") (pinfunction "O_3") (pintype "output"))
      (node (ref "IC6") (pin "5") (pinfunction "I1_5") (pintype "input"))
    )
    (net (code "68") (name "Net-(IC6C-I0)") (class "Default")
      (node (ref "IC6") (pin "9") (pinfunction "I0_9") (pintype "input"))
      (node (ref "R2") (pin "2") (pinfunction "2_2") (pintype "passive"))
      (node (ref "U11") (pin "P4") (pinfunction "READY_P4") (pintype "bidirectional"))
    )
    (net (code "69") (name "Net-(IC6C-I1)") (class "Default")
      (node (ref "IC6") (pin "10") (pinfunction "I1_10") (pintype "input"))
      (node (ref "R6") (pin "2") (pinfunction "2_2") (pintype "passive"))
      (node (ref "U4") (pin "P4") (pinfunction "READY_P4") (pintype "bidirectional"))
    )
    (net (code "70") (name "Net-(IC6C-O)") (class "Default")
      (node (ref "IC6") (pin "12") (pinfunction "I0_12") (pintype "input"))
      (node (ref "IC6") (pin "13") (pinfunction "I1_13") (pintype "input"))
      (node (ref "IC6") (pin "8") (pinfunction "O_8") (pintype "output"))
    )
    (net (code "71") (name "Net-(IC6D-O)") (class "Default")
      (node (ref "IC6") (pin "11") (pinfunction "O_11") (pintype "output"))
      (node (ref "U$1") (pin "P$33") (pinfunction "WAIT*_P$33") (pintype "bidirectional"))
    )
    (net (code "72") (name "Net-(IC8A-A1)") (class "Default")
      (node (ref "IC8") (pin "2") (pinfunction "A1_2") (pintype "input"))
      (node (ref "JOYSTICK1") (pin "2") (pinfunction "2_2") (pintype "passive"))
      (node (ref "RN1") (pin "13") (pinfunction "13_13") (pintype "passive"))
    )
    (net (code "73") (name "Net-(IC8A-A2)") (class "Default")
      (node (ref "IC8") (pin "4") (pinfunction "A2_4") (pintype "input"))
      (node (ref "JOYSTICK1") (pin "3") (pinfunction "3_3") (pintype "passive"))
      (node (ref "RN1") (pin "12") (pinfunction "12_12") (pintype "passive"))
    )
    (net (code "74") (name "Net-(IC8A-A3)") (class "Default")
      (node (ref "IC8") (pin "6") (pinfunction "A3_6") (pintype "input"))
      (node (ref "JOYSTICK1") (pin "4") (pinfunction "4_4") (pintype "passive"))
      (node (ref "RN1") (pin "11") (pinfunction "11_11") (pintype "passive"))
    )
    (net (code "75") (name "Net-(IC8A-A4)") (class "Default")
      (node (ref "IC8") (pin "8") (pinfunction "A4_8") (pintype "input"))
      (node (ref "JOYSTICK1") (pin "5") (pinfunction "5_5") (pintype "passive"))
      (node (ref "RN1") (pin "10") (pinfunction "10_10") (pintype "passive"))
    )
    (net (code "76") (name "Net-(IC8B-A1)") (class "Default")
      (node (ref "IC8") (pin "11") (pinfunction "A1_11") (pintype "input"))
      (node (ref "JOYSTICK1") (pin "9") (pinfunction "9_9") (pintype "passive"))
      (node (ref "RN1") (pin "9") (pinfunction "9_9") (pintype "passive"))
    )
    (net (code "77") (name "Net-(J4-PadPIN)") (class "Default")
      (node (ref "J4") (pin "PIN") (pinfunction "PIN_PIN") (pintype "bidirectional"))
      (node (ref "J4") (pin "SWITCH") (pinfunction "SWITCH_SWITCH") (pintype "bidirectional"))
      (node (ref "R5") (pin "2") (pinfunction "2_2") (pintype "passive"))
    )
    (net (code "78") (name "Net-(J5-PadPIN)") (class "Default")
      (node (ref "J5") (pin "PIN") (pinfunction "PIN_PIN") (pintype "bidirectional"))
      (node (ref "J5") (pin "SWITCH") (pinfunction "SWITCH_SWITCH") (pintype "bidirectional"))
      (node (ref "R1") (pin "2") (pinfunction "2_2") (pintype "passive"))
    )
    (net (code "79") (name "Net-(R8-E)") (class "Default")
      (node (ref "Q2") (pin "E") (pinfunction "E_E") (pintype "passive"))
      (node (ref "R3") (pin "1") (pinfunction "1_1") (pintype "passive"))
      (node (ref "R8") (pin "3") (pinfunction "E_3") (pintype "passive"))
    )
    (net (code "80") (name "Net-(R8-S)") (class "Default")
      (node (ref "J3") (pin "PIN") (pinfunction "PIN_PIN") (pintype "bidirectional"))
      (node (ref "J3") (pin "SWITCH") (pinfunction "SWITCH_SWITCH") (pintype "bidirectional"))
      (node (ref "R8") (pin "2") (pinfunction "S_2") (pintype "passive"))
    )
    (net (code "81") (name "Net-(REG1-VIN)") (class "Default")
      (node (ref "C5") (pin "+") (pinfunction "+_+") (pintype "passive"))
      (node (ref "REG1") (pin "P$1") (pinfunction "VIN_P$1") (pintype "bidirectional"))
      (node (ref "S1") (pin "1") (pinfunction "O_1") (pintype "passive"))
    )
    (net (code "82") (name "Net-(S1-P)") (class "Default")
      (node (ref "S1") (pin "2") (pinfunction "P_2") (pintype "passive"))
      (node (ref "U$2") (pin "3") (pinfunction "3_3") (pintype "passive"))
    )
    (net (code "83") (name "Net-(U$1-INT*)") (class "Default")
      (node (ref "JP1") (pin "1") (pinfunction "1_1") (pintype "passive"))
      (node (ref "U$1") (pin "P$21") (pinfunction "INT*_P$21") (pintype "bidirectional"))
    )
    (net (code "84") (name "Net-(U1-A0)") (class "Default")
      (node (ref "U1") (pin "14") (pinfunction "A0_14") (pintype "bidirectional"))
      (node (ref "U2") (pin "P3") (pinfunction "AD7_P3") (pintype "bidirectional"))
      (node (ref "U3") (pin "14") (pinfunction "A0_14") (pintype "bidirectional"))
    )
    (net (code "85") (name "Net-(U1-A1)") (class "Default")
      (node (ref "U1") (pin "13") (pinfunction "A1_13") (pintype "bidirectional"))
      (node (ref "U2") (pin "P4") (pinfunction "AD6_P4") (pintype "bidirectional"))
      (node (ref "U3") (pin "13") (pinfunction "A1_13") (pintype "bidirectional"))
    )
    (net (code "86") (name "Net-(U1-A2)") (class "Default")
      (node (ref "U1") (pin "12") (pinfunction "A2_12") (pintype "bidirectional"))
      (node (ref "U2") (pin "P5") (pinfunction "AD5_P5") (pintype "bidirectional"))
      (node (ref "U3") (pin "12") (pinfunction "A2_12") (pintype "bidirectional"))
    )
    (net (code "87") (name "Net-(U1-A3)") (class "Default")
      (node (ref "U1") (pin "11") (pinfunction "A3_11") (pintype "bidirectional"))
      (node (ref "U2") (pin "P6") (pinfunction "AD4_P6") (pintype "bidirectional"))
      (node (ref "U3") (pin "11") (pinfunction "A3_11") (pintype "bidirectional"))
    )
    (net (code "88") (name "Net-(U1-A4)") (class "Default")
      (node (ref "U1") (pin "8") (pinfunction "A4_8") (pintype "bidirectional"))
      (node (ref "U2") (pin "P7") (pinfunction "AD3_P7") (pintype "bidirectional"))
      (node (ref "U3") (pin "8") (pinfunction "A4_8") (pintype "bidirectional"))
    )
    (net (code "89") (name "Net-(U1-A5)") (class "Default")
      (node (ref "U1") (pin "7") (pinfunction "A5_7") (pintype "bidirectional"))
      (node (ref "U2") (pin "P8") (pinfunction "AD2_P8") (pintype "bidirectional"))
      (node (ref "U3") (pin "7") (pinfunction "A5_7") (pintype "bidirectional"))
    )
    (net (code "90") (name "Net-(U1-A6)") (class "Default")
      (node (ref "U1") (pin "6") (pinfunction "A6_6") (pintype "bidirectional"))
      (node (ref "U2") (pin "P9") (pinfunction "AD1_P9") (pintype "bidirectional"))
      (node (ref "U3") (pin "6") (pinfunction "A6_6") (pintype "bidirectional"))
    )
    (net (code "91") (name "Net-(U1-A7)") (class "Default")
      (node (ref "U1") (pin "10") (pinfunction "A7_10") (pintype "bidirectional"))
      (node (ref "U2") (pin "P10") (pinfunction "AD0_P10") (pintype "bidirectional"))
      (node (ref "U3") (pin "10") (pinfunction "A7_10") (pintype "bidirectional"))
    )
    (net (code "92") (name "Net-(U1-CAS*)") (class "Default")
      (node (ref "U1") (pin "16") (pinfunction "CAS*_16") (pintype "bidirectional"))
      (node (ref "U2") (pin "P2") (pinfunction "CAS*_P2") (pintype "bidirectional"))
      (node (ref "U3") (pin "16") (pinfunction "CAS*_16") (pintype "bidirectional"))
    )
    (net (code "93") (name "Net-(U1-DQ1)") (class "Default")
      (node (ref "U1") (pin "2") (pinfunction "DQ1_2") (pintype "bidirectional"))
      (node (ref "U2") (pin "P32") (pinfunction "RD0_P32") (pintype "bidirectional"))
    )
    (net (code "94") (name "Net-(U1-DQ2)") (class "Default")
      (node (ref "U1") (pin "3") (pinfunction "DQ2_3") (pintype "bidirectional"))
      (node (ref "U2") (pin "P31") (pinfunction "RD1_P31") (pintype "bidirectional"))
    )
    (net (code "95") (name "Net-(U1-DQ3)") (class "Default")
      (node (ref "U1") (pin "15") (pinfunction "DQ3_15") (pintype "bidirectional"))
      (node (ref "U2") (pin "P30") (pinfunction "RD2_P30") (pintype "bidirectional"))
    )
    (net (code "96") (name "Net-(U1-DQ4)") (class "Default")
      (node (ref "U1") (pin "17") (pinfunction "DQ4_17") (pintype "bidirectional"))
      (node (ref "U2") (pin "P29") (pinfunction "RD3_P29") (pintype "bidirectional"))
    )
    (net (code "97") (name "Net-(U1-RAS*)") (class "Default")
      (node (ref "U1") (pin "5") (pinfunction "RAS*_5") (pintype "bidirectional"))
      (node (ref "U2") (pin "P1") (pinfunction "RAS*_P1") (pintype "bidirectional"))
      (node (ref "U3") (pin "5") (pinfunction "RAS*_5") (pintype "bidirectional"))
    )
    (net (code "98") (name "Net-(U1-W*)") (class "Default")
      (node (ref "U1") (pin "4") (pinfunction "W*_4") (pintype "bidirectional"))
      (node (ref "U2") (pin "P11") (pinfunction "R/W*_P11") (pintype "bidirectional"))
      (node (ref "U3") (pin "4") (pinfunction "W*_4") (pintype "bidirectional"))
    )
    (net (code "99") (name "Net-(U2-COMVID)") (class "Default")
      (node (ref "Q2") (pin "B") (pinfunction "B_B") (pintype "passive"))
      (node (ref "R4") (pin "1") (pinfunction "1_1") (pintype "passive"))
      (node (ref "U2") (pin "P36") (pinfunction "COMVID_P36") (pintype "bidirectional"))
    )
    (net (code "100") (name "Net-(U2-EXTVDP)") (class "Default")
      (node (ref "J2") (pin "PIN") (pinfunction "PIN_PIN") (pintype "bidirectional"))
      (node (ref "J2") (pin "SWITCH") (pinfunction "SWITCH_SWITCH") (pintype "bidirectional"))
      (node (ref "U2") (pin "P35") (pinfunction "EXTVDP_P35") (pintype "bidirectional"))
    )
    (net (code "101") (name "Net-(U2-INT*)") (class "Default")
      (node (ref "JP1") (pin "2") (pinfunction "2_2") (pintype "passive"))
      (node (ref "U2") (pin "P16") (pinfunction "INT*_P16") (pintype "bidirectional"))
    )
    (net (code "102") (name "Net-(U2-RD4)") (class "Default")
      (node (ref "U2") (pin "P28") (pinfunction "RD4_P28") (pintype "bidirectional"))
      (node (ref "U3") (pin "2") (pinfunction "DQ1_2") (pintype "bidirectional"))
    )
    (net (code "103") (name "Net-(U2-RD5)") (class "Default")
      (node (ref "U2") (pin "P27") (pinfunction "RD5_P27") (pintype "bidirectional"))
      (node (ref "U3") (pin "3") (pinfunction "DQ2_3") (pintype "bidirectional"))
    )
    (net (code "104") (name "Net-(U2-RD6)") (class "Default")
      (node (ref "U2") (pin "P26") (pinfunction "RD6_P26") (pintype "bidirectional"))
      (node (ref "U3") (pin "15") (pinfunction "DQ3_15") (pintype "bidirectional"))
    )
    (net (code "105") (name "Net-(U2-RD7)") (class "Default")
      (node (ref "U2") (pin "P25") (pinfunction "RD7_P25") (pintype "bidirectional"))
      (node (ref "U3") (pin "17") (pinfunction "DQ4_17") (pintype "bidirectional"))
    )
    (net (code "106") (name "Net-(U2-XTAL1)") (class "Default")
      (node (ref "C9") (pin "2") (pinfunction "2_2") (pintype "passive"))
      (node (ref "Q1") (pin "1") (pinfunction "1_1") (pintype "passive"))
      (node (ref "U2") (pin "P40") (pinfunction "XTAL1_P40") (pintype "bidirectional"))
    )
    (net (code "107") (name "Net-(U4-SNDOUT)") (class "Default")
      (node (ref "C1") (pin "+") (pinfunction "+_+") (pintype "passive"))
      (node (ref "U4") (pin "P7") (pinfunction "SNDOUT_P7") (pintype "bidirectional"))
    )
    (net (code "108") (name "Net-(U11-CLOCK)") (class "Default")
      (node (ref "U11") (pin "P14") (pinfunction "CLOCK_P14") (pintype "bidirectional"))
      (node (ref "U2") (pin "P38") (pinfunction "CPUCLK_P38") (pintype "bidirectional"))
      (node (ref "U4") (pin "P14") (pinfunction "CLOCK_P14") (pintype "bidirectional"))
    )
    (net (code "109") (name "Net-(U11-SNDOUT)") (class "Default")
      (node (ref "C27") (pin "+") (pinfunction "+_+") (pintype "passive"))
      (node (ref "U11") (pin "P7") (pinfunction "SNDOUT_P7") (pintype "bidirectional"))
    )
    (net (code "110") (name "VCC") (class "Default")
      (node (ref "ATF22V10C") (pin "24") (pinfunction "VCC_24") (pintype "bidirectional"))
      (node (ref "C10") (pin "1") (pinfunction "1_1") (pintype "passive"))
      (node (ref "C12") (pin "1") (pinfunction "1_1") (pintype "passive"))
      (node (ref "C13") (pin "1") (pinfunction "1_1") (pintype "passive"))
      (node (ref "C14") (pin "1") (pinfunction "1_1") (pintype "passive"))
      (node (ref "C15") (pin "1") (pinfunction "1_1") (pintype "passive"))
      (node (ref "C16") (pin "1") (pinfunction "1_1") (pintype "passive"))
      (node (ref "C17") (pin "1") (pinfunction "1_1") (pintype "passive"))
      (node (ref "C20") (pin "1") (pinfunction "1_1") (pintype "passive"))
      (node (ref "C21") (pin "1") (pinfunction "1_1") (pintype "passive"))
      (node (ref "C4") (pin "+") (pinfunction "+_+") (pintype "passive"))
      (node (ref "C6") (pin "1") (pinfunction "1_1") (pintype "passive"))
      (node (ref "C7") (pin "1") (pinfunction "1_1") (pintype "passive"))
      (node (ref "C8") (pin "1") (pinfunction "1_1") (pintype "passive"))
      (node (ref "IC1") (pin "20") (pinfunction "VCC_20") (pintype "power_in"))
      (node (ref "IC3") (pin "28") (pinfunction "VCC_28") (pintype "power_in"))
      (node (ref "IC4") (pin "20") (pinfunction "VCC_20") (pintype "power_in"))
      (node (ref "IC5") (pin "20") (pinfunction "VCC_20") (pintype "power_in"))
      (node (ref "IC6") (pin "14") (pinfunction "VCC_14") (pintype "power_in"))
      (node (ref "IC6") (pin "2") (pinfunction "I1_2") (pintype "input"))
      (node (ref "IC8") (pin "20") (pinfunction "VCC_20") (pintype "power_in"))
      (node (ref "Q2") (pin "C") (pinfunction "C_C") (pintype "passive"))
      (node (ref "R2") (pin "1") (pinfunction "1_1") (pintype "passive"))
      (node (ref "R6") (pin "1") (pinfunction "1_1") (pintype "passive"))
      (node (ref "R7") (pin "1") (pinfunction "1_1") (pintype "passive"))
      (node (ref "R9") (pin "2") (pinfunction "2_2") (pintype "passive"))
      (node (ref "REG1") (pin "P$3") (pinfunction "VOUT_P$3") (pintype "bidirectional"))
      (node (ref "RN1") (pin "1") (pinfunction "1_1") (pintype "passive"))
      (node (ref "U1") (pin "9") (pinfunction "VDD_9") (pintype "bidirectional"))
      (node (ref "U11") (pin "P16") (pinfunction "VCC_P16") (pintype "bidirectional"))
      (node (ref "U2") (pin "P33") (pinfunction "VDD_P33") (pintype "bidirectional"))
      (node (ref "U3") (pin "9") (pinfunction "VDD_9") (pintype "bidirectional"))
      (node (ref "U4") (pin "P16") (pinfunction "VCC_P16") (pintype "bidirectional"))
    )
    (net (code "111") (name "unconnected-(ATF22V10C-NC-Pad1)") (class "Default")
      (node (ref "ATF22V10C") (pin "1") (pinfunction "NC_1") (pintype "bidirectional"))
    )
    (net (code "112") (name "unconnected-(ATF22V10C-NC2-Pad4)") (class "Default")
      (node (ref "ATF22V10C") (pin "4") (pinfunction "NC2_4") (pintype "bidirectional"))
    )
    (net (code "113") (name "unconnected-(ATF22V10C-NC5-Pad23)") (class "Default")
      (node (ref "ATF22V10C") (pin "23") (pinfunction "NC5_23") (pintype "bidirectional"))
    )
    (net (code "114") (name "unconnected-(JOYSTICK1-Pad1)") (class "Default")
      (node (ref "JOYSTICK1") (pin "1") (pinfunction "1_1") (pintype "passive"))
    )
    (net (code "115") (name "unconnected-(JOYSTICK1-Pad6)") (class "Default")
      (node (ref "JOYSTICK1") (pin "6") (pinfunction "6_6") (pintype "passive"))
    )
    (net (code "116") (name "unconnected-(JOYSTICK1-Pad8)") (class "Default")
      (node (ref "JOYSTICK1") (pin "8") (pinfunction "8_8") (pintype "passive"))
    )
    (net (code "117") (name "unconnected-(JOYSTICK2-Pad1)") (class "Default")
      (node (ref "JOYSTICK2") (pin "1") (pinfunction "1_1") (pintype "passive"))
    )
    (net (code "118") (name "unconnected-(JOYSTICK2-Pad6)") (class "Default")
      (node (ref "JOYSTICK2") (pin "6") (pinfunction "6_6") (pintype "passive"))
    )
    (net (code "119") (name "unconnected-(JOYSTICK2-Pad8)") (class "Default")
      (node (ref "JOYSTICK2") (pin "8") (pinfunction "8_8") (pintype "passive"))
    )
    (net (code "120") (name "unconnected-(R8-A-Pad1)") (class "Default")
      (node (ref "R8") (pin "1") (pinfunction "A_1") (pintype "passive"))
    )
    (net (code "121") (name "unconnected-(RN1-Pad2)") (class "Default")
      (node (ref "RN1") (pin "2") (pinfunction "2_2") (pintype "passive"))
    )
    (net (code "122") (name "unconnected-(S1-S-Pad3)") (class "Default")
      (node (ref "S1") (pin "3") (pinfunction "S_3") (pintype "passive"))
    )
    (net (code "123") (name "unconnected-(U$1-CAS*-PadP$3)") (class "Default")
      (node (ref "U$1") (pin "P$3") (pinfunction "CAS*_P$3") (pintype "bidirectional"))
    )
    (net (code "124") (name "unconnected-(U$1-GND3-PadP$37)") (class "Default")
      (node (ref "U$1") (pin "P$37") (pinfunction "GND3_P$37") (pintype "bidirectional"))
    )
    (net (code "125") (name "unconnected-(U$1-INTAK*-PadP$14)") (class "Default")
      (node (ref "U$1") (pin "P$14") (pinfunction "INTAK*_P$14") (pintype "bidirectional"))
    )
    (net (code "126") (name "unconnected-(U$1-MUX-PadP$16)") (class "Default")
      (node (ref "U$1") (pin "P$16") (pinfunction "MUX_P$16") (pintype "bidirectional"))
    )
    (net (code "127") (name "unconnected-(U$1-NC-PadP$39)") (class "Default")
      (node (ref "U$1") (pin "P$39") (pinfunction "NC_P$39") (pintype "bidirectional"))
    )
    (net (code "128") (name "unconnected-(U$1-TEST*-PadP$23)") (class "Default")
      (node (ref "U$1") (pin "P$23") (pinfunction "TEST*_P$23") (pintype "bidirectional"))
    )
    (net (code "129") (name "unconnected-(U2-NC-PadP37)") (class "Default")
      (node (ref "U2") (pin "P37") (pinfunction "NC_P37") (pintype "bidirectional"))
    )
    (net (code "130") (name "unconnected-(U4-NC-PadP9)") (class "Default")
      (node (ref "U4") (pin "P9") (pinfunction "NC_P9") (pintype "bidirectional"))
    )
    (net (code "131") (name "unconnected-(U11-NC-PadP9)") (class "Default")
      (node (ref "U11") (pin "P9") (pinfunction "NC_P9") (pintype "bidirectional"))
    )
  )
)
